# AGC_INDIC.net
KiCad netlist of a schematic drawn in EAGLE
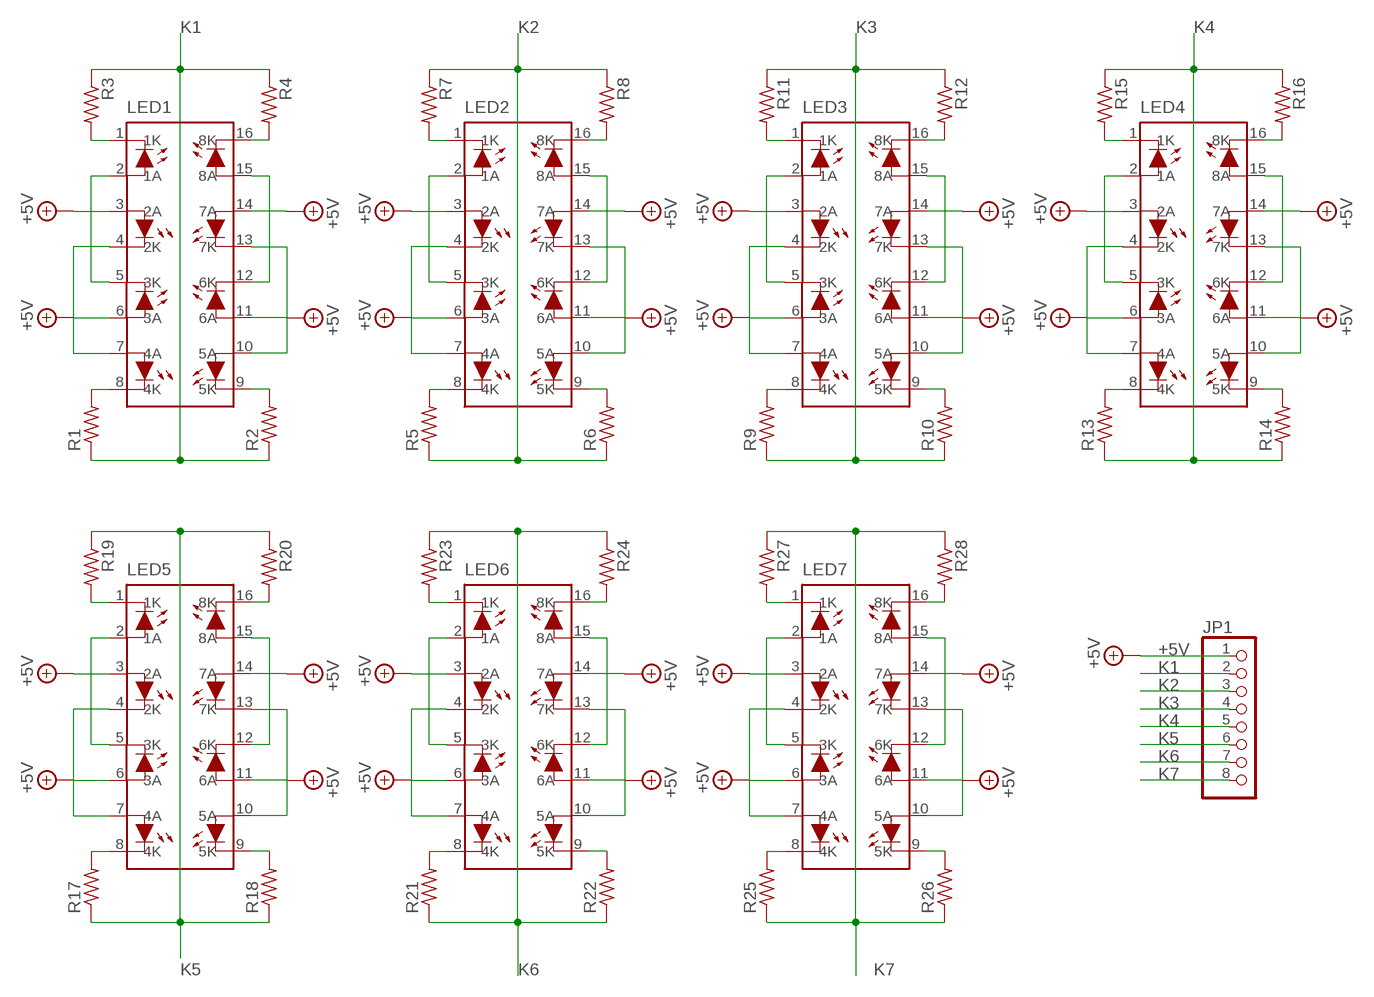
[diagram p0: schematic, sheet 1]

(export (version "E")
  (design (tool "Eeschema 10.0.6"))
  (components
    (comp (ref "JP1")
      (value "PINHD-1X8")
      (footprint "eagle-import:1X08")
      (libsource (lib "eagle-import") (part "PINHD-1X8"))
    )
    (comp (ref "LED1")
      (value "HCLP-E")
      (footprint "eagle-import:E100-16")
      (libsource (lib "eagle-import") (part "HCLP-E"))
    )
    (comp (ref "LED2")
      (value "HCLP-E")
      (footprint "eagle-import:E100-16")
      (libsource (lib "eagle-import") (part "HCLP-E"))
    )
    (comp (ref "LED3")
      (value "HCLP-E")
      (footprint "eagle-import:E100-16")
      (libsource (lib "eagle-import") (part "HCLP-E"))
    )
    (comp (ref "LED4")
      (value "HCLP-E")
      (footprint "eagle-import:E100-16")
      (libsource (lib "eagle-import") (part "HCLP-E"))
    )
    (comp (ref "LED5")
      (value "HCLP-E")
      (footprint "eagle-import:E100-16")
      (libsource (lib "eagle-import") (part "HCLP-E"))
    )
    (comp (ref "LED6")
      (value "HCLP-E")
      (footprint "eagle-import:E100-16")
      (libsource (lib "eagle-import") (part "HCLP-E"))
    )
    (comp (ref "LED7")
      (value "HCLP-E")
      (footprint "eagle-import:E100-16")
      (libsource (lib "eagle-import") (part "HCLP-E"))
    )
    (comp (ref "R1")
      (value "R-US_0204/5")
      (footprint "eagle-import:0204_5")
      (libsource (lib "eagle-import") (part "R-US_0204/5"))
    )
    (comp (ref "R2")
      (value "R-US_0204/5")
      (footprint "eagle-import:0204_5")
      (libsource (lib "eagle-import") (part "R-US_0204/5"))
    )
    (comp (ref "R3")
      (value "R-US_0204/5")
      (footprint "eagle-import:0204_5")
      (libsource (lib "eagle-import") (part "R-US_0204/5"))
    )
    (comp (ref "R4")
      (value "R-US_0204/5")
      (footprint "eagle-import:0204_5")
      (libsource (lib "eagle-import") (part "R-US_0204/5"))
    )
    (comp (ref "R5")
      (value "R-US_0204/5")
      (footprint "eagle-import:0204_5")
      (libsource (lib "eagle-import") (part "R-US_0204/5"))
    )
    (comp (ref "R6")
      (value "R-US_0204/5")
      (footprint "eagle-import:0204_5")
      (libsource (lib "eagle-import") (part "R-US_0204/5"))
    )
    (comp (ref "R7")
      (value "R-US_0204/5")
      (footprint "eagle-import:0204_5")
      (libsource (lib "eagle-import") (part "R-US_0204/5"))
    )
    (comp (ref "R8")
      (value "R-US_0204/5")
      (footprint "eagle-import:0204_5")
      (libsource (lib "eagle-import") (part "R-US_0204/5"))
    )
    (comp (ref "R9")
      (value "R-US_0204/5")
      (footprint "eagle-import:0204_5")
      (libsource (lib "eagle-import") (part "R-US_0204/5"))
    )
    (comp (ref "R10")
      (value "R-US_0204/5")
      (footprint "eagle-import:0204_5")
      (libsource (lib "eagle-import") (part "R-US_0204/5"))
    )
    (comp (ref "R11")
      (value "R-US_0204/5")
      (footprint "eagle-import:0204_5")
      (libsource (lib "eagle-import") (part "R-US_0204/5"))
    )
    (comp (ref "R12")
      (value "R-US_0204/5")
      (footprint "eagle-import:0204_5")
      (libsource (lib "eagle-import") (part "R-US_0204/5"))
    )
    (comp (ref "R13")
      (value "R-US_0204/5")
      (footprint "eagle-import:0204_5")
      (libsource (lib "eagle-import") (part "R-US_0204/5"))
    )
    (comp (ref "R14")
      (value "R-US_0204/5")
      (footprint "eagle-import:0204_5")
      (libsource (lib "eagle-import") (part "R-US_0204/5"))
    )
    (comp (ref "R15")
      (value "R-US_0204/5")
      (footprint "eagle-import:0204_5")
      (libsource (lib "eagle-import") (part "R-US_0204/5"))
    )
    (comp (ref "R16")
      (value "R-US_0204/5")
      (footprint "eagle-import:0204_5")
      (libsource (lib "eagle-import") (part "R-US_0204/5"))
    )
    (comp (ref "R17")
      (value "R-US_0204/5")
      (footprint "eagle-import:0204_5")
      (libsource (lib "eagle-import") (part "R-US_0204/5"))
    )
    (comp (ref "R18")
      (value "R-US_0204/5")
      (footprint "eagle-import:0204_5")
      (libsource (lib "eagle-import") (part "R-US_0204/5"))
    )
    (comp (ref "R19")
      (value "R-US_0204/5")
      (footprint "eagle-import:0204_5")
      (libsource (lib "eagle-import") (part "R-US_0204/5"))
    )
    (comp (ref "R20")
      (value "R-US_0204/5")
      (footprint "eagle-import:0204_5")
      (libsource (lib "eagle-import") (part "R-US_0204/5"))
    )
    (comp (ref "R21")
      (value "R-US_0204/5")
      (footprint "eagle-import:0204_5")
      (libsource (lib "eagle-import") (part "R-US_0204/5"))
    )
    (comp (ref "R22")
      (value "R-US_0204/5")
      (footprint "eagle-import:0204_5")
      (libsource (lib "eagle-import") (part "R-US_0204/5"))
    )
    (comp (ref "R23")
      (value "R-US_0204/5")
      (footprint "eagle-import:0204_5")
      (libsource (lib "eagle-import") (part "R-US_0204/5"))
    )
    (comp (ref "R24")
      (value "R-US_0204/5")
      (footprint "eagle-import:0204_5")
      (libsource (lib "eagle-import") (part "R-US_0204/5"))
    )
    (comp (ref "R25")
      (value "R-US_0204/5")
      (footprint "eagle-import:0204_5")
      (libsource (lib "eagle-import") (part "R-US_0204/5"))
    )
    (comp (ref "R26")
      (value "R-US_0204/5")
      (footprint "eagle-import:0204_5")
      (libsource (lib "eagle-import") (part "R-US_0204/5"))
    )
    (comp (ref "R27")
      (value "R-US_0204/5")
      (footprint "eagle-import:0204_5")
      (libsource (lib "eagle-import") (part "R-US_0204/5"))
    )
    (comp (ref "R28")
      (value "R-US_0204/5")
      (footprint "eagle-import:0204_5")
      (libsource (lib "eagle-import") (part "R-US_0204/5"))
    )
  )
  (nets
    (net (code "1") (name "+5V") (class "Default")
      (node (ref "JP1") (pin "1") (pinfunction "1_1") (pintype "passive"))
      (node (ref "LED1") (pin "11") (pinfunction "6A_11") (pintype "passive"))
      (node (ref "LED1") (pin "14") (pinfunction "7A_14") (pintype "passive"))
      (node (ref "LED1") (pin "3") (pinfunction "2A_3") (pintype "passive"))
      (node (ref "LED1") (pin "6") (pinfunction "3A_6") (pintype "passive"))
      (node (ref "LED2") (pin "11") (pinfunction "6A_11") (pintype "passive"))
      (node (ref "LED2") (pin "14") (pinfunction "7A_14") (pintype "passive"))
      (node (ref "LED2") (pin "3") (pinfunction "2A_3") (pintype "passive"))
      (node (ref "LED2") (pin "6") (pinfunction "3A_6") (pintype "passive"))
      (node (ref "LED3") (pin "11") (pinfunction "6A_11") (pintype "passive"))
      (node (ref "LED3") (pin "14") (pinfunction "7A_14") (pintype "passive"))
      (node (ref "LED3") (pin "3") (pinfunction "2A_3") (pintype "passive"))
      (node (ref "LED3") (pin "6") (pinfunction "3A_6") (pintype "passive"))
      (node (ref "LED4") (pin "11") (pinfunction "6A_11") (pintype "passive"))
      (node (ref "LED4") (pin "14") (pinfunction "7A_14") (pintype "passive"))
      (node (ref "LED4") (pin "3") (pinfunction "2A_3") (pintype "passive"))
      (node (ref "LED4") (pin "6") (pinfunction "3A_6") (pintype "passive"))
      (node (ref "LED5") (pin "11") (pinfunction "6A_11") (pintype "passive"))
      (node (ref "LED5") (pin "14") (pinfunction "7A_14") (pintype "passive"))
      (node (ref "LED5") (pin "3") (pinfunction "2A_3") (pintype "passive"))
      (node (ref "LED5") (pin "6") (pinfunction "3A_6") (pintype "passive"))
      (node (ref "LED6") (pin "11") (pinfunction "6A_11") (pintype "passive"))
      (node (ref "LED6") (pin "14") (pinfunction "7A_14") (pintype "passive"))
      (node (ref "LED6") (pin "3") (pinfunction "2A_3") (pintype "passive"))
      (node (ref "LED6") (pin "6") (pinfunction "3A_6") (pintype "passive"))
      (node (ref "LED7") (pin "11") (pinfunction "6A_11") (pintype "passive"))
      (node (ref "LED7") (pin "14") (pinfunction "7A_14") (pintype "passive"))
      (node (ref "LED7") (pin "3") (pinfunction "2A_3") (pintype "passive"))
      (node (ref "LED7") (pin "6") (pinfunction "3A_6") (pintype "passive"))
    )
    (net (code "2") (name "/K1") (class "Default")
      (node (ref "JP1") (pin "2") (pinfunction "2_2") (pintype "passive"))
      (node (ref "R1") (pin "1") (pinfunction "1_1") (pintype "passive"))
      (node (ref "R2") (pin "1") (pinfunction "1_1") (pintype "passive"))
      (node (ref "R3") (pin "1") (pinfunction "1_1") (pintype "passive"))
      (node (ref "R4") (pin "1") (pinfunction "1_1") (pintype "passive"))
    )
    (net (code "3") (name "/K2") (class "Default")
      (node (ref "JP1") (pin "3") (pinfunction "3_3") (pintype "passive"))
      (node (ref "R5") (pin "1") (pinfunction "1_1") (pintype "passive"))
      (node (ref "R6") (pin "1") (pinfunction "1_1") (pintype "passive"))
      (node (ref "R7") (pin "1") (pinfunction "1_1") (pintype "passive"))
      (node (ref "R8") (pin "1") (pinfunction "1_1") (pintype "passive"))
    )
    (net (code "4") (name "/K3") (class "Default")
      (node (ref "JP1") (pin "4") (pinfunction "4_4") (pintype "passive"))
      (node (ref "R10") (pin "1") (pinfunction "1_1") (pintype "passive"))
      (node (ref "R11") (pin "1") (pinfunction "1_1") (pintype "passive"))
      (node (ref "R12") (pin "1") (pinfunction "1_1") (pintype "passive"))
      (node (ref "R9") (pin "1") (pinfunction "1_1") (pintype "passive"))
    )
    (net (code "5") (name "/K4") (class "Default")
      (node (ref "JP1") (pin "5") (pinfunction "5_5") (pintype "passive"))
      (node (ref "R13") (pin "1") (pinfunction "1_1") (pintype "passive"))
      (node (ref "R14") (pin "1") (pinfunction "1_1") (pintype "passive"))
      (node (ref "R15") (pin "1") (pinfunction "1_1") (pintype "passive"))
      (node (ref "R16") (pin "1") (pinfunction "1_1") (pintype "passive"))
    )
    (net (code "6") (name "/K5") (class "Default")
      (node (ref "JP1") (pin "6") (pinfunction "6_6") (pintype "passive"))
      (node (ref "R17") (pin "1") (pinfunction "1_1") (pintype "passive"))
      (node (ref "R18") (pin "1") (pinfunction "1_1") (pintype "passive"))
      (node (ref "R19") (pin "1") (pinfunction "1_1") (pintype "passive"))
      (node (ref "R20") (pin "1") (pinfunction "1_1") (pintype "passive"))
    )
    (net (code "7") (name "/K6") (class "Default")
      (node (ref "JP1") (pin "7") (pinfunction "7_7") (pintype "passive"))
      (node (ref "R21") (pin "1") (pinfunction "1_1") (pintype "passive"))
      (node (ref "R22") (pin "1") (pinfunction "1_1") (pintype "passive"))
      (node (ref "R23") (pin "1") (pinfunction "1_1") (pintype "passive"))
      (node (ref "R24") (pin "1") (pinfunction "1_1") (pintype "passive"))
    )
    (net (code "8") (name "/K7") (class "Default")
      (node (ref "JP1") (pin "8") (pinfunction "8_8") (pintype "passive"))
      (node (ref "R25") (pin "1") (pinfunction "1_1") (pintype "passive"))
      (node (ref "R26") (pin "1") (pinfunction "1_1") (pintype "passive"))
      (node (ref "R27") (pin "1") (pinfunction "1_1") (pintype "passive"))
      (node (ref "R28") (pin "1") (pinfunction "1_1") (pintype "passive"))
    )
    (net (code "9") (name "Net-(LED1-1A)") (class "Default")
      (node (ref "LED1") (pin "2") (pinfunction "1A_2") (pintype "passive"))
      (node (ref "LED1") (pin "5") (pinfunction "3K_5") (pintype "passive"))
    )
    (net (code "10") (name "Net-(LED1-1K)") (class "Default")
      (node (ref "LED1") (pin "1") (pinfunction "1K_1") (pintype "passive"))
      (node (ref "R3") (pin "2") (pinfunction "2_2") (pintype "passive"))
    )
    (net (code "11") (name "Net-(LED1-2K)") (class "Default")
      (node (ref "LED1") (pin "4") (pinfunction "2K_4") (pintype "passive"))
      (node (ref "LED1") (pin "7") (pinfunction "4A_7") (pintype "passive"))
    )
    (net (code "12") (name "Net-(LED1-4K)") (class "Default")
      (node (ref "LED1") (pin "8") (pinfunction "4K_8") (pintype "passive"))
      (node (ref "R1") (pin "2") (pinfunction "2_2") (pintype "passive"))
    )
    (net (code "13") (name "Net-(LED1-5A)") (class "Default")
      (node (ref "LED1") (pin "10") (pinfunction "5A_10") (pintype "passive"))
      (node (ref "LED1") (pin "13") (pinfunction "7K_13") (pintype "passive"))
    )
    (net (code "14") (name "Net-(LED1-5K)") (class "Default")
      (node (ref "LED1") (pin "9") (pinfunction "5K_9") (pintype "passive"))
      (node (ref "R2") (pin "2") (pinfunction "2_2") (pintype "passive"))
    )
    (net (code "15") (name "Net-(LED1-6K)") (class "Default")
      (node (ref "LED1") (pin "12") (pinfunction "6K_12") (pintype "passive"))
      (node (ref "LED1") (pin "15") (pinfunction "8A_15") (pintype "passive"))
    )
    (net (code "16") (name "Net-(LED1-8K)") (class "Default")
      (node (ref "LED1") (pin "16") (pinfunction "8K_16") (pintype "passive"))
      (node (ref "R4") (pin "2") (pinfunction "2_2") (pintype "passive"))
    )
    (net (code "17") (name "Net-(LED2-1A)") (class "Default")
      (node (ref "LED2") (pin "2") (pinfunction "1A_2") (pintype "passive"))
      (node (ref "LED2") (pin "5") (pinfunction "3K_5") (pintype "passive"))
    )
    (net (code "18") (name "Net-(LED2-1K)") (class "Default")
      (node (ref "LED2") (pin "1") (pinfunction "1K_1") (pintype "passive"))
      (node (ref "R7") (pin "2") (pinfunction "2_2") (pintype "passive"))
    )
    (net (code "19") (name "Net-(LED2-2K)") (class "Default")
      (node (ref "LED2") (pin "4") (pinfunction "2K_4") (pintype "passive"))
      (node (ref "LED2") (pin "7") (pinfunction "4A_7") (pintype "passive"))
    )
    (net (code "20") (name "Net-(LED2-4K)") (class "Default")
      (node (ref "LED2") (pin "8") (pinfunction "4K_8") (pintype "passive"))
      (node (ref "R5") (pin "2") (pinfunction "2_2") (pintype "passive"))
    )
    (net (code "21") (name "Net-(LED2-5A)") (class "Default")
      (node (ref "LED2") (pin "10") (pinfunction "5A_10") (pintype "passive"))
      (node (ref "LED2") (pin "13") (pinfunction "7K_13") (pintype "passive"))
    )
    (net (code "22") (name "Net-(LED2-5K)") (class "Default")
      (node (ref "LED2") (pin "9") (pinfunction "5K_9") (pintype "passive"))
      (node (ref "R6") (pin "2") (pinfunction "2_2") (pintype "passive"))
    )
    (net (code "23") (name "Net-(LED2-6K)") (class "Default")
      (node (ref "LED2") (pin "12") (pinfunction "6K_12") (pintype "passive"))
      (node (ref "LED2") (pin "15") (pinfunction "8A_15") (pintype "passive"))
    )
    (net (code "24") (name "Net-(LED2-8K)") (class "Default")
      (node (ref "LED2") (pin "16") (pinfunction "8K_16") (pintype "passive"))
      (node (ref "R8") (pin "2") (pinfunction "2_2") (pintype "passive"))
    )
    (net (code "25") (name "Net-(LED3-1A)") (class "Default")
      (node (ref "LED3") (pin "2") (pinfunction "1A_2") (pintype "passive"))
      (node (ref "LED3") (pin "5") (pinfunction "3K_5") (pintype "passive"))
    )
    (net (code "26") (name "Net-(LED3-1K)") (class "Default")
      (node (ref "LED3") (pin "1") (pinfunction "1K_1") (pintype "passive"))
      (node (ref "R11") (pin "2") (pinfunction "2_2") (pintype "passive"))
    )
    (net (code "27") (name "Net-(LED3-2K)") (class "Default")
      (node (ref "LED3") (pin "4") (pinfunction "2K_4") (pintype "passive"))
      (node (ref "LED3") (pin "7") (pinfunction "4A_7") (pintype "passive"))
    )
    (net (code "28") (name "Net-(LED3-4K)") (class "Default")
      (node (ref "LED3") (pin "8") (pinfunction "4K_8") (pintype "passive"))
      (node (ref "R9") (pin "2") (pinfunction "2_2") (pintype "passive"))
    )
    (net (code "29") (name "Net-(LED3-5A)") (class "Default")
      (node (ref "LED3") (pin "10") (pinfunction "5A_10") (pintype "passive"))
      (node (ref "LED3") (pin "13") (pinfunction "7K_13") (pintype "passive"))
    )
    (net (code "30") (name "Net-(LED3-5K)") (class "Default")
      (node (ref "LED3") (pin "9") (pinfunction "5K_9") (pintype "passive"))
      (node (ref "R10") (pin "2") (pinfunction "2_2") (pintype "passive"))
    )
    (net (code "31") (name "Net-(LED3-6K)") (class "Default")
      (node (ref "LED3") (pin "12") (pinfunction "6K_12") (pintype "passive"))
      (node (ref "LED3") (pin "15") (pinfunction "8A_15") (pintype "passive"))
    )
    (net (code "32") (name "Net-(LED3-8K)") (class "Default")
      (node (ref "LED3") (pin "16") (pinfunction "8K_16") (pintype "passive"))
      (node (ref "R12") (pin "2") (pinfunction "2_2") (pintype "passive"))
    )
    (net (code "33") (name "Net-(LED4-1A)") (class "Default")
      (node (ref "LED4") (pin "2") (pinfunction "1A_2") (pintype "passive"))
      (node (ref "LED4") (pin "5") (pinfunction "3K_5") (pintype "passive"))
    )
    (net (code "34") (name "Net-(LED4-1K)") (class "Default")
      (node (ref "LED4") (pin "1") (pinfunction "1K_1") (pintype "passive"))
      (node (ref "R15") (pin "2") (pinfunction "2_2") (pintype "passive"))
    )
    (net (code "35") (name "Net-(LED4-2K)") (class "Default")
      (node (ref "LED4") (pin "4") (pinfunction "2K_4") (pintype "passive"))
      (node (ref "LED4") (pin "7") (pinfunction "4A_7") (pintype "passive"))
    )
    (net (code "36") (name "Net-(LED4-4K)") (class "Default")
      (node (ref "LED4") (pin "8") (pinfunction "4K_8") (pintype "passive"))
      (node (ref "R13") (pin "2") (pinfunction "2_2") (pintype "passive"))
    )
    (net (code "37") (name "Net-(LED4-5A)") (class "Default")
      (node (ref "LED4") (pin "10") (pinfunction "5A_10") (pintype "passive"))
      (node (ref "LED4") (pin "13") (pinfunction "7K_13") (pintype "passive"))
    )
    (net (code "38") (name "Net-(LED4-5K)") (class "Default")
      (node (ref "LED4") (pin "9") (pinfunction "5K_9") (pintype "passive"))
      (node (ref "R14") (pin "2") (pinfunction "2_2") (pintype "passive"))
    )
    (net (code "39") (name "Net-(LED4-6K)") (class "Default")
      (node (ref "LED4") (pin "12") (pinfunction "6K_12") (pintype "passive"))
      (node (ref "LED4") (pin "15") (pinfunction "8A_15") (pintype "passive"))
    )
    (net (code "40") (name "Net-(LED4-8K)") (class "Default")
      (node (ref "LED4") (pin "16") (pinfunction "8K_16") (pintype "passive"))
      (node (ref "R16") (pin "2") (pinfunction "2_2") (pintype "passive"))
    )
    (net (code "41") (name "Net-(LED5-1A)") (class "Default")
      (node (ref "LED5") (pin "2") (pinfunction "1A_2") (pintype "passive"))
      (node (ref "LED5") (pin "5") (pinfunction "3K_5") (pintype "passive"))
    )
    (net (code "42") (name "Net-(LED5-1K)") (class "Default")
      (node (ref "LED5") (pin "1") (pinfunction "1K_1") (pintype "passive"))
      (node (ref "R19") (pin "2") (pinfunction "2_2") (pintype "passive"))
    )
    (net (code "43") (name "Net-(LED5-2K)") (class "Default")
      (node (ref "LED5") (pin "4") (pinfunction "2K_4") (pintype "passive"))
      (node (ref "LED5") (pin "7") (pinfunction "4A_7") (pintype "passive"))
    )
    (net (code "44") (name "Net-(LED5-4K)") (class "Default")
      (node (ref "LED5") (pin "8") (pinfunction "4K_8") (pintype "passive"))
      (node (ref "R17") (pin "2") (pinfunction "2_2") (pintype "passive"))
    )
    (net (code "45") (name "Net-(LED5-5A)") (class "Default")
      (node (ref "LED5") (pin "10") (pinfunction "5A_10") (pintype "passive"))
      (node (ref "LED5") (pin "13") (pinfunction "7K_13") (pintype "passive"))
    )
    (net (code "46") (name "Net-(LED5-5K)") (class "Default")
      (node (ref "LED5") (pin "9") (pinfunction "5K_9") (pintype "passive"))
      (node (ref "R18") (pin "2") (pinfunction "2_2") (pintype "passive"))
    )
    (net (code "47") (name "Net-(LED5-6K)") (class "Default")
      (node (ref "LED5") (pin "12") (pinfunction "6K_12") (pintype "passive"))
      (node (ref "LED5") (pin "15") (pinfunction "8A_15") (pintype "passive"))
    )
    (net (code "48") (name "Net-(LED5-8K)") (class "Default")
      (node (ref "LED5") (pin "16") (pinfunction "8K_16") (pintype "passive"))
      (node (ref "R20") (pin "2") (pinfunction "2_2") (pintype "passive"))
    )
    (net (code "49") (name "Net-(LED6-1A)") (class "Default")
      (node (ref "LED6") (pin "2") (pinfunction "1A_2") (pintype "passive"))
      (node (ref "LED6") (pin "5") (pinfunction "3K_5") (pintype "passive"))
    )
    (net (code "50") (name "Net-(LED6-1K)") (class "Default")
      (node (ref "LED6") (pin "1") (pinfunction "1K_1") (pintype "passive"))
      (node (ref "R23") (pin "2") (pinfunction "2_2") (pintype "passive"))
    )
    (net (code "51") (name "Net-(LED6-2K)") (class "Default")
      (node (ref "LED6") (pin "4") (pinfunction "2K_4") (pintype "passive"))
      (node (ref "LED6") (pin "7") (pinfunction "4A_7") (pintype "passive"))
    )
    (net (code "52") (name "Net-(LED6-4K)") (class "Default")
      (node (ref "LED6") (pin "8") (pinfunction "4K_8") (pintype "passive"))
      (node (ref "R21") (pin "2") (pinfunction "2_2") (pintype "passive"))
    )
    (net (code "53") (name "Net-(LED6-5A)") (class "Default")
      (node (ref "LED6") (pin "10") (pinfunction "5A_10") (pintype "passive"))
      (node (ref "LED6") (pin "13") (pinfunction "7K_13") (pintype "passive"))
    )
    (net (code "54") (name "Net-(LED6-5K)") (class "Default")
      (node (ref "LED6") (pin "9") (pinfunction "5K_9") (pintype "passive"))
      (node (ref "R22") (pin "2") (pinfunction "2_2") (pintype "passive"))
    )
    (net (code "55") (name "Net-(LED6-6K)") (class "Default")
      (node (ref "LED6") (pin "12") (pinfunction "6K_12") (pintype "passive"))
      (node (ref "LED6") (pin "15") (pinfunction "8A_15") (pintype "passive"))
    )
    (net (code "56") (name "Net-(LED6-8K)") (class "Default")
      (node (ref "LED6") (pin "16") (pinfunction "8K_16") (pintype "passive"))
      (node (ref "R24") (pin "2") (pinfunction "2_2") (pintype "passive"))
    )
    (net (code "57") (name "Net-(LED7-1A)") (class "Default")
      (node (ref "LED7") (pin "2") (pinfunction "1A_2") (pintype "passive"))
      (node (ref "LED7") (pin "5") (pinfunction "3K_5") (pintype "passive"))
    )
    (net (code "58") (name "Net-(LED7-1K)") (class "Default")
      (node (ref "LED7") (pin "1") (pinfunction "1K_1") (pintype "passive"))
      (node (ref "R27") (pin "2") (pinfunction "2_2") (pintype "passive"))
    )
    (net (code "59") (name "Net-(LED7-2K)") (class "Default")
      (node (ref "LED7") (pin "4") (pinfunction "2K_4") (pintype "passive"))
      (node (ref "LED7") (pin "7") (pinfunction "4A_7") (pintype "passive"))
    )
    (net (code "60") (name "Net-(LED7-4K)") (class "Default")
      (node (ref "LED7") (pin "8") (pinfunction "4K_8") (pintype "passive"))
      (node (ref "R25") (pin "2") (pinfunction "2_2") (pintype "passive"))
    )
    (net (code "61") (name "Net-(LED7-5A)") (class "Default")
      (node (ref "LED7") (pin "10") (pinfunction "5A_10") (pintype "passive"))
      (node (ref "LED7") (pin "13") (pinfunction "7K_13") (pintype "passive"))
    )
    (net (code "62") (name "Net-(LED7-5K)") (class "Default")
      (node (ref "LED7") (pin "9") (pinfunction "5K_9") (pintype "passive"))
      (node (ref "R26") (pin "2") (pinfunction "2_2") (pintype "passive"))
    )
    (net (code "63") (name "Net-(LED7-6K)") (class "Default")
      (node (ref "LED7") (pin "12") (pinfunction "6K_12") (pintype "passive"))
      (node (ref "LED7") (pin "15") (pinfunction "8A_15") (pintype "passive"))
    )
    (net (code "64") (name "Net-(LED7-8K)") (class "Default")
      (node (ref "LED7") (pin "16") (pinfunction "8K_16") (pintype "passive"))
      (node (ref "R28") (pin "2") (pinfunction "2_2") (pintype "passive"))
    )
  )
)
